# 4-20.net
KiCad netlist of a schematic drawn in Altium Designer
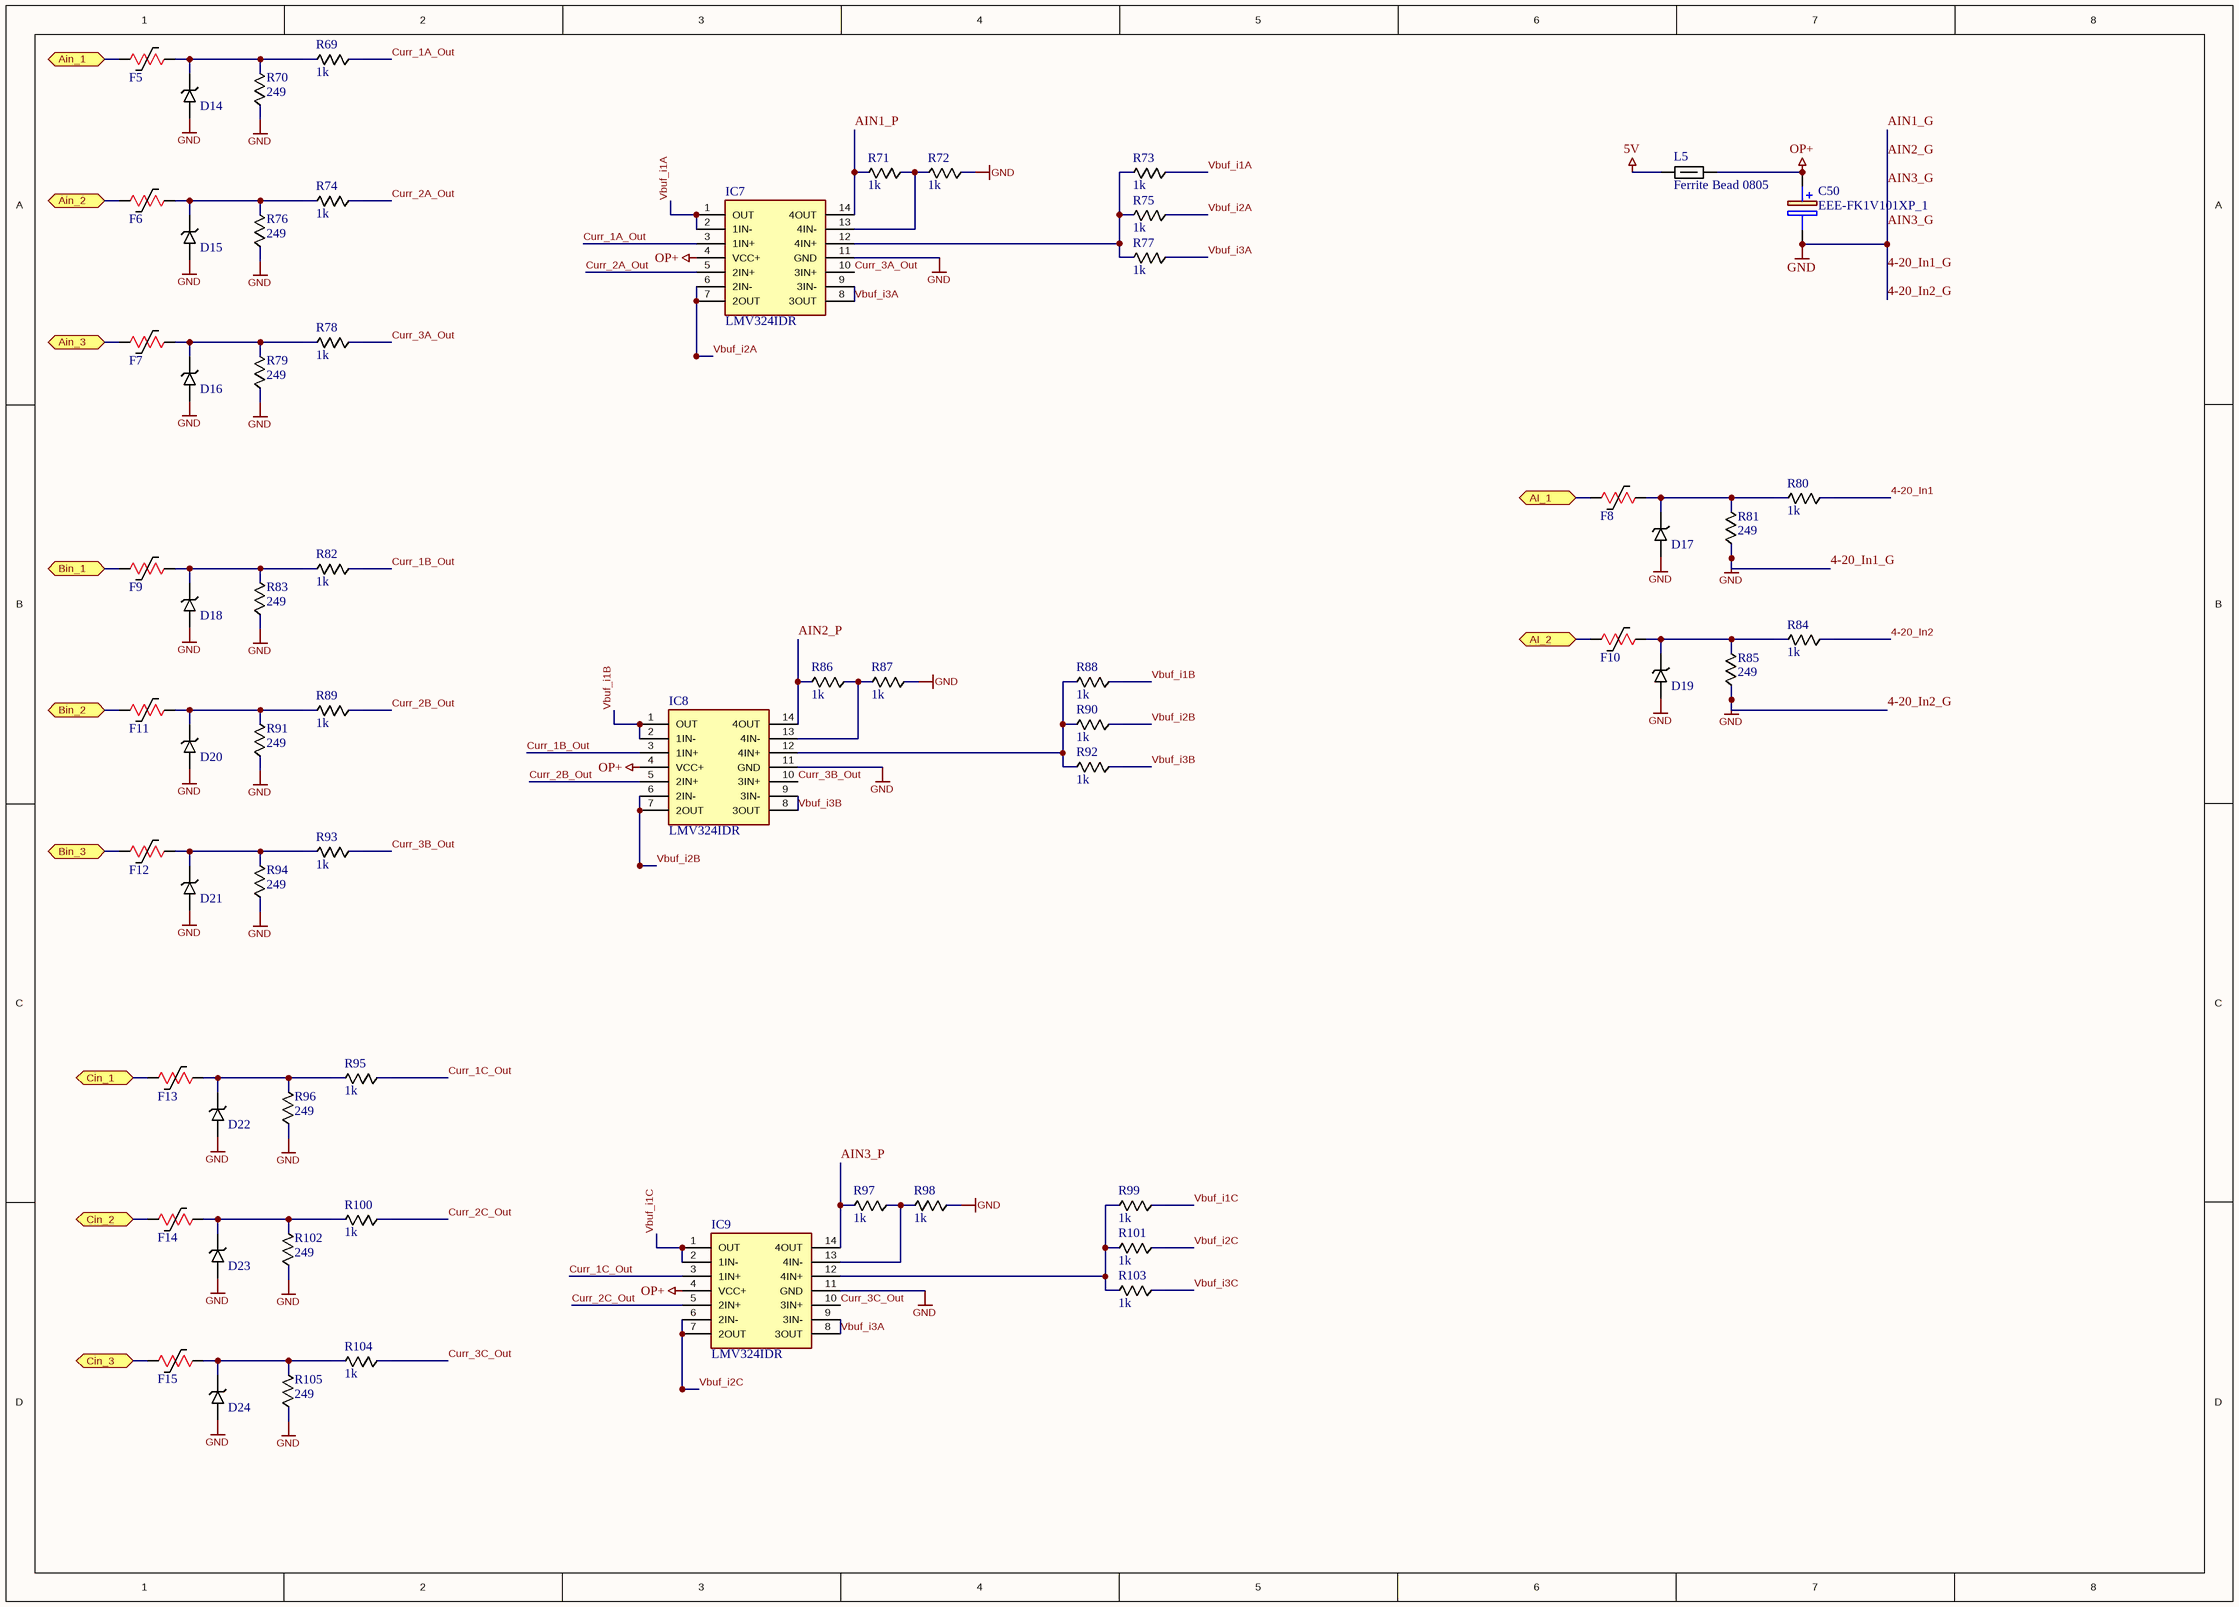
[diagram p0: 4-20.SchDoc]

(export (version "E")
  (design (tool "Eeschema 10.0.6"))
  (components
    (comp (ref "C50")
      (value "EEE-FK1V101XP_1")
      (footprint "IGAS Elements:EEE1AA220WR")
      (description "EEEFK1C100R")
      (fields
        (field (name "MANUFACTURER_PART_NUMBER") "EEE-FK1V101XP")
        (field (name "MOUSER PART NUMBER") "667-EEE-FK1V101XP")
      )
      (libsource (lib "IGAS Elements") (part "EEE-FK1V101XP_1"))
    )
    (comp (ref "D14")
      (value "TVS Diode")
      (footprint "DO-214AC / SMA - POL")
      (description "PESD5V0U1UB")
      (libsource (lib "IGAS Elements") (part "TVS_1_Uni_1"))
    )
    (comp (ref "D15")
      (value "TVS Diode")
      (footprint "DO-214AC / SMA - POL")
      (description "PESD5V0U1UB")
      (libsource (lib "IGAS Elements") (part "TVS_1_Uni_1"))
    )
    (comp (ref "D16")
      (value "TVS Diode")
      (footprint "DO-214AC / SMA - POL")
      (description "PESD5V0U1UB")
      (libsource (lib "IGAS Elements") (part "TVS_1_Uni_1"))
    )
    (comp (ref "D17")
      (value "TVS Diode")
      (footprint "DO-214AC / SMA - POL")
      (description "PESD5V0U1UB")
      (libsource (lib "IGAS Elements") (part "TVS_1_Uni_1"))
    )
    (comp (ref "D18")
      (value "TVS Diode")
      (footprint "DO-214AC / SMA - POL")
      (description "PESD5V0U1UB")
      (libsource (lib "IGAS Elements") (part "TVS_1_Uni_1"))
    )
    (comp (ref "D19")
      (value "TVS Diode")
      (footprint "DO-214AC / SMA - POL")
      (description "PESD5V0U1UB")
      (libsource (lib "IGAS Elements") (part "TVS_1_Uni_1"))
    )
    (comp (ref "D20")
      (value "TVS Diode")
      (footprint "DO-214AC / SMA - POL")
      (description "PESD5V0U1UB")
      (libsource (lib "IGAS Elements") (part "TVS_1_Uni_1"))
    )
    (comp (ref "D21")
      (value "TVS Diode")
      (footprint "DO-214AC / SMA - POL")
      (description "PESD5V0U1UB")
      (libsource (lib "IGAS Elements") (part "TVS_1_Uni_1"))
    )
    (comp (ref "D22")
      (value "TVS Diode")
      (footprint "DO-214AC / SMA - POL")
      (description "PESD5V0U1UB")
      (libsource (lib "IGAS Elements") (part "TVS_1_Uni_1"))
    )
    (comp (ref "D23")
      (value "TVS Diode")
      (footprint "DO-214AC / SMA - POL")
      (description "PESD5V0U1UB")
      (libsource (lib "IGAS Elements") (part "TVS_1_Uni_1"))
    )
    (comp (ref "D24")
      (value "TVS Diode")
      (footprint "DO-214AC / SMA - POL")
      (description "PESD5V0U1UB")
      (libsource (lib "IGAS Elements") (part "TVS_1_Uni_1"))
    )
    (comp (ref "F5")
      (value "MF-USMF005-2")
      (footprint "MF-MSMF030-2")
      (description "Resettable Fuse Polyswitch")
      (libsource (lib "IGAS Elements") (part "Fuse Resettable"))
    )
    (comp (ref "F6")
      (value "MF-USMF005-2")
      (footprint "MF-MSMF030-2")
      (description "Resettable Fuse Polyswitch")
      (libsource (lib "IGAS Elements") (part "Fuse Resettable"))
    )
    (comp (ref "F7")
      (value "MF-USMF005-2")
      (footprint "MF-MSMF030-2")
      (description "Resettable Fuse Polyswitch")
      (libsource (lib "IGAS Elements") (part "Fuse Resettable"))
    )
    (comp (ref "F8")
      (value "MF-USMF005-2")
      (footprint "MF-MSMF030-2")
      (description "Resettable Fuse Polyswitch")
      (libsource (lib "IGAS Elements") (part "Fuse Resettable"))
    )
    (comp (ref "F9")
      (value "MF-USMF005-2")
      (footprint "MF-MSMF030-2")
      (description "Resettable Fuse Polyswitch")
      (libsource (lib "IGAS Elements") (part "Fuse Resettable"))
    )
    (comp (ref "F10")
      (value "MF-USMF005-2")
      (footprint "MF-MSMF030-2")
      (description "Resettable Fuse Polyswitch")
      (libsource (lib "IGAS Elements") (part "Fuse Resettable"))
    )
    (comp (ref "F11")
      (value "MF-USMF005-2")
      (footprint "MF-MSMF030-2")
      (description "Resettable Fuse Polyswitch")
      (libsource (lib "IGAS Elements") (part "Fuse Resettable"))
    )
    (comp (ref "F12")
      (value "MF-USMF005-2")
      (footprint "MF-MSMF030-2")
      (description "Resettable Fuse Polyswitch")
      (libsource (lib "IGAS Elements") (part "Fuse Resettable"))
    )
    (comp (ref "F13")
      (value "MF-USMF005-2")
      (footprint "MF-MSMF030-2")
      (description "Resettable Fuse Polyswitch")
      (libsource (lib "IGAS Elements") (part "Fuse Resettable"))
    )
    (comp (ref "F14")
      (value "MF-USMF005-2")
      (footprint "MF-MSMF030-2")
      (description "Resettable Fuse Polyswitch")
      (libsource (lib "IGAS Elements") (part "Fuse Resettable"))
    )
    (comp (ref "F15")
      (value "MF-USMF005-2")
      (footprint "MF-MSMF030-2")
      (description "Resettable Fuse Polyswitch")
      (libsource (lib "IGAS Elements") (part "Fuse Resettable"))
    )
    (comp (ref "IC7")
      (value "LMV324IDR")
      (footprint "IGAS Elements:SOIC14N")
      (description "Integrated Circuit")
      (fields (field (name "MOUSER PART NUMBER") "595-LMV324IDR"))
      (libsource (lib "IGAS Elements") (part "LMV324IDR"))
    )
    (comp (ref "IC8")
      (value "LMV324IDR")
      (footprint "IGAS Elements:SOIC14N")
      (description "Integrated Circuit")
      (fields (field (name "MOUSER PART NUMBER") "595-LMV324IDR"))
      (libsource (lib "IGAS Elements") (part "LMV324IDR"))
    )
    (comp (ref "IC9")
      (value "LMV324IDR")
      (footprint "IGAS Elements:SOIC14N")
      (description "Integrated Circuit")
      (fields (field (name "MOUSER PART NUMBER") "595-LMV324IDR"))
      (libsource (lib "IGAS Elements") (part "LMV324IDR"))
    )
    (comp (ref "L5")
      (value "Ferrite Bead 0805")
      (footprint "BLM21AG102BH1J")
      (libsource (lib "IGAS Elements") (part "Ferrite Bead"))
    )
    (comp (ref "R69") (value "1k") (footprint "0603 CAP") (libsource (lib "IGAS Elements") (part "0603 RES")))
    (comp (ref "R70")
      (value "249")
      (footprint "1206 Res")
      (description "RC1206FR-07249RL")
      (libsource (lib "IGAS Elements") (part "RES 1206"))
    )
    (comp (ref "R71") (value "1k") (footprint "0603 CAP") (libsource (lib "IGAS Elements") (part "0603 RES")))
    (comp (ref "R72") (value "1k") (footprint "0603 CAP") (libsource (lib "IGAS Elements") (part "0603 RES")))
    (comp (ref "R73") (value "1k") (footprint "0603 CAP") (libsource (lib "IGAS Elements") (part "0603 RES")))
    (comp (ref "R74") (value "1k") (footprint "0603 CAP") (libsource (lib "IGAS Elements") (part "0603 RES")))
    (comp (ref "R75") (value "1k") (footprint "0603 CAP") (libsource (lib "IGAS Elements") (part "0603 RES")))
    (comp (ref "R76")
      (value "249")
      (footprint "1206 Res Kelvin")
      (description "RT1206BRD07249RL")
      (libsource (lib "IGAS Elements") (part "RES 1206"))
    )
    (comp (ref "R77") (value "1k") (footprint "0603 CAP") (libsource (lib "IGAS Elements") (part "0603 RES")))
    (comp (ref "R78") (value "1k") (footprint "0603 CAP") (libsource (lib "IGAS Elements") (part "0603 RES")))
    (comp (ref "R79")
      (value "249")
      (footprint "1206 Res Kelvin")
      (description "RT1206BRD07249RL")
      (libsource (lib "IGAS Elements") (part "RES 1206"))
    )
    (comp (ref "R80") (value "1k") (footprint "0603 CAP") (libsource (lib "IGAS Elements") (part "0603 RES")))
    (comp (ref "R81")
      (value "249")
      (footprint "1206 Res Kelvin")
      (description "RT1206BRD07249RL")
      (libsource (lib "IGAS Elements") (part "RES 1206"))
    )
    (comp (ref "R82") (value "1k") (footprint "0603 CAP") (libsource (lib "IGAS Elements") (part "0603 RES")))
    (comp (ref "R83")
      (value "249")
      (footprint "1206 Res Kelvin")
      (description "RT1206BRD07249RL")
      (libsource (lib "IGAS Elements") (part "RES 1206"))
    )
    (comp (ref "R84") (value "1k") (footprint "0603 CAP") (libsource (lib "IGAS Elements") (part "0603 RES")))
    (comp (ref "R85")
      (value "249")
      (footprint "1206 Res Kelvin")
      (description "RT1206BRD07249RL")
      (libsource (lib "IGAS Elements") (part "RES 1206"))
    )
    (comp (ref "R86") (value "1k") (footprint "0603 CAP") (libsource (lib "IGAS Elements") (part "0603 RES")))
    (comp (ref "R87") (value "1k") (footprint "0603 CAP") (libsource (lib "IGAS Elements") (part "0603 RES")))
    (comp (ref "R88") (value "1k") (footprint "0603 CAP") (libsource (lib "IGAS Elements") (part "0603 RES")))
    (comp (ref "R89") (value "1k") (footprint "0603 CAP") (libsource (lib "IGAS Elements") (part "0603 RES")))
    (comp (ref "R90") (value "1k") (footprint "0603 CAP") (libsource (lib "IGAS Elements") (part "0603 RES")))
    (comp (ref "R91")
      (value "249")
      (footprint "1206 Res Kelvin")
      (description "RT1206BRD07249RL")
      (libsource (lib "IGAS Elements") (part "RES 1206"))
    )
    (comp (ref "R92") (value "1k") (footprint "0603 CAP") (libsource (lib "IGAS Elements") (part "0603 RES")))
    (comp (ref "R93") (value "1k") (footprint "0603 CAP") (libsource (lib "IGAS Elements") (part "0603 RES")))
    (comp (ref "R94")
      (value "249")
      (footprint "1206 Res Kelvin")
      (description "RT1206BRD07249RL")
      (libsource (lib "IGAS Elements") (part "RES 1206"))
    )
    (comp (ref "R95") (value "1k") (footprint "0603 CAP") (libsource (lib "IGAS Elements") (part "0603 RES")))
    (comp (ref "R96")
      (value "249")
      (footprint "1206 Res Kelvin")
      (description "RT1206BRD07249RL")
      (libsource (lib "IGAS Elements") (part "RES 1206"))
    )
    (comp (ref "R97") (value "1k") (footprint "0603 CAP") (libsource (lib "IGAS Elements") (part "0603 RES")))
    (comp (ref "R98") (value "1k") (footprint "0603 CAP") (libsource (lib "IGAS Elements") (part "0603 RES")))
    (comp (ref "R99") (value "1k") (footprint "0603 CAP") (libsource (lib "IGAS Elements") (part "0603 RES")))
    (comp (ref "R100")
      (value "1k")
      (footprint "0603 CAP")
      (libsource (lib "IGAS Elements") (part "0603 RES"))
    )
    (comp (ref "R101")
      (value "1k")
      (footprint "0603 CAP")
      (libsource (lib "IGAS Elements") (part "0603 RES"))
    )
    (comp (ref "R102")
      (value "249")
      (footprint "1206 Res Kelvin")
      (description "RT1206BRD07249RL")
      (libsource (lib "IGAS Elements") (part "RES 1206"))
    )
    (comp (ref "R103")
      (value "1k")
      (footprint "0603 CAP")
      (libsource (lib "IGAS Elements") (part "0603 RES"))
    )
    (comp (ref "R104")
      (value "1k")
      (footprint "0603 CAP")
      (libsource (lib "IGAS Elements") (part "0603 RES"))
    )
    (comp (ref "R105")
      (value "249")
      (footprint "1206 Res Kelvin")
      (description "RT1206BRD07249RL")
      (libsource (lib "IGAS Elements") (part "RES 1206"))
    )
  )
  (nets
    (net (code "1") (name "/4-20_In1") (class "Default") (node (ref "R80") (pin "1") (pintype "passive")))
    (net (code "2") (name "/4-20_In2") (class "Default") (node (ref "R84") (pin "1") (pintype "passive")))
    (net (code "3") (name "/AIN1_P") (class "Default")
      (node (ref "IC7") (pin "14") (pinfunction "4OUT_14") (pintype "passive"))
      (node (ref "R71") (pin "2") (pintype "passive"))
    )
    (net (code "4") (name "/AIN2_P") (class "Default")
      (node (ref "IC8") (pin "14") (pinfunction "4OUT_14") (pintype "passive"))
      (node (ref "R86") (pin "2") (pintype "passive"))
    )
    (net (code "5") (name "/AIN3_P") (class "Default")
      (node (ref "IC9") (pin "14") (pinfunction "4OUT_14") (pintype "passive"))
      (node (ref "R97") (pin "2") (pintype "passive"))
    )
    (net (code "6") (name "/AI_1") (class "Default")
      (node (ref "F8") (pin "2") (pinfunction "2_2") (pintype "passive"))
    )
    (net (code "7") (name "/AI_2") (class "Default")
      (node (ref "F10") (pin "2") (pinfunction "2_2") (pintype "passive"))
    )
    (net (code "8") (name "/Ain_1") (class "Default")
      (node (ref "F5") (pin "2") (pinfunction "2_2") (pintype "passive"))
    )
    (net (code "9") (name "/Ain_2") (class "Default")
      (node (ref "F6") (pin "2") (pinfunction "2_2") (pintype "passive"))
    )
    (net (code "10") (name "/Ain_3") (class "Default")
      (node (ref "F7") (pin "2") (pinfunction "2_2") (pintype "passive"))
    )
    (net (code "11") (name "/Bin_1") (class "Default")
      (node (ref "F9") (pin "2") (pinfunction "2_2") (pintype "passive"))
    )
    (net (code "12") (name "/Bin_2") (class "Default")
      (node (ref "F11") (pin "2") (pinfunction "2_2") (pintype "passive"))
    )
    (net (code "13") (name "/Bin_3") (class "Default")
      (node (ref "F12") (pin "2") (pinfunction "2_2") (pintype "passive"))
    )
    (net (code "14") (name "/Cin_1") (class "Default")
      (node (ref "F13") (pin "2") (pinfunction "2_2") (pintype "passive"))
    )
    (net (code "15") (name "/Cin_2") (class "Default")
      (node (ref "F14") (pin "2") (pinfunction "2_2") (pintype "passive"))
    )
    (net (code "16") (name "/Cin_3") (class "Default")
      (node (ref "F15") (pin "2") (pinfunction "2_2") (pintype "passive"))
    )
    (net (code "17") (name "/Curr_1A_Out") (class "Default")
      (node (ref "IC7") (pin "3") (pinfunction "1IN+_3") (pintype "passive"))
      (node (ref "R69") (pin "1") (pintype "passive"))
    )
    (net (code "18") (name "/Curr_1B_Out") (class "Default")
      (node (ref "IC8") (pin "3") (pinfunction "1IN+_3") (pintype "passive"))
      (node (ref "R82") (pin "1") (pintype "passive"))
    )
    (net (code "19") (name "/Curr_1C_Out") (class "Default")
      (node (ref "IC9") (pin "3") (pinfunction "1IN+_3") (pintype "passive"))
      (node (ref "R95") (pin "1") (pintype "passive"))
    )
    (net (code "20") (name "/Curr_2A_Out") (class "Default")
      (node (ref "IC7") (pin "5") (pinfunction "2IN+_5") (pintype "passive"))
      (node (ref "R74") (pin "1") (pintype "passive"))
    )
    (net (code "21") (name "/Curr_2B_Out") (class "Default")
      (node (ref "IC8") (pin "5") (pinfunction "2IN+_5") (pintype "passive"))
      (node (ref "R89") (pin "1") (pintype "passive"))
    )
    (net (code "22") (name "/Curr_2C_Out") (class "Default")
      (node (ref "IC9") (pin "5") (pinfunction "2IN+_5") (pintype "passive"))
      (node (ref "R100") (pin "1") (pintype "passive"))
    )
    (net (code "23") (name "/Curr_3A_Out") (class "Default")
      (node (ref "IC7") (pin "10") (pinfunction "3IN+_10") (pintype "passive"))
      (node (ref "R78") (pin "1") (pintype "passive"))
    )
    (net (code "24") (name "/Curr_3B_Out") (class "Default")
      (node (ref "IC8") (pin "10") (pinfunction "3IN+_10") (pintype "passive"))
      (node (ref "R93") (pin "1") (pintype "passive"))
    )
    (net (code "25") (name "/Curr_3C_Out") (class "Default")
      (node (ref "IC9") (pin "10") (pinfunction "3IN+_10") (pintype "passive"))
      (node (ref "R104") (pin "1") (pintype "passive"))
    )
    (net (code "26") (name "/Vbuf_i1A") (class "Default")
      (node (ref "IC7") (pin "1") (pinfunction "OUT_1") (pintype "passive"))
      (node (ref "IC7") (pin "2") (pinfunction "1IN-_2") (pintype "passive"))
      (node (ref "R73") (pin "1") (pintype "passive"))
    )
    (net (code "27") (name "/Vbuf_i1B") (class "Default")
      (node (ref "IC8") (pin "1") (pinfunction "OUT_1") (pintype "passive"))
      (node (ref "IC8") (pin "2") (pinfunction "1IN-_2") (pintype "passive"))
      (node (ref "R88") (pin "1") (pintype "passive"))
    )
    (net (code "28") (name "/Vbuf_i1C") (class "Default")
      (node (ref "IC9") (pin "1") (pinfunction "OUT_1") (pintype "passive"))
      (node (ref "IC9") (pin "2") (pinfunction "1IN-_2") (pintype "passive"))
      (node (ref "R99") (pin "1") (pintype "passive"))
    )
    (net (code "29") (name "/Vbuf_i2A") (class "Default")
      (node (ref "IC7") (pin "6") (pinfunction "2IN-_6") (pintype "passive"))
      (node (ref "IC7") (pin "7") (pinfunction "2OUT_7") (pintype "passive"))
      (node (ref "R75") (pin "1") (pintype "passive"))
    )
    (net (code "30") (name "/Vbuf_i2B") (class "Default")
      (node (ref "IC8") (pin "6") (pinfunction "2IN-_6") (pintype "passive"))
      (node (ref "IC8") (pin "7") (pinfunction "2OUT_7") (pintype "passive"))
      (node (ref "R90") (pin "1") (pintype "passive"))
    )
    (net (code "31") (name "/Vbuf_i2C") (class "Default")
      (node (ref "IC9") (pin "6") (pinfunction "2IN-_6") (pintype "passive"))
      (node (ref "IC9") (pin "7") (pinfunction "2OUT_7") (pintype "passive"))
      (node (ref "R101") (pin "1") (pintype "passive"))
    )
    (net (code "32") (name "/Vbuf_i3A") (class "Default")
      (node (ref "IC7") (pin "8") (pinfunction "3OUT_8") (pintype "passive"))
      (node (ref "IC7") (pin "9") (pinfunction "3IN-_9") (pintype "passive"))
      (node (ref "IC9") (pin "8") (pinfunction "3OUT_8") (pintype "passive"))
      (node (ref "IC9") (pin "9") (pinfunction "3IN-_9") (pintype "passive"))
      (node (ref "R77") (pin "1") (pintype "passive"))
    )
    (net (code "33") (name "/Vbuf_i3B") (class "Default")
      (node (ref "IC8") (pin "8") (pinfunction "3OUT_8") (pintype "passive"))
      (node (ref "IC8") (pin "9") (pinfunction "3IN-_9") (pintype "passive"))
      (node (ref "R92") (pin "1") (pintype "passive"))
    )
    (net (code "34") (name "/Vbuf_i3C") (class "Default") (node (ref "R103") (pin "1") (pintype "passive")))
    (net (code "35") (name "5V") (class "Default")
      (node (ref "L5") (pin "1") (pinfunction "1_1") (pintype "passive"))
    )
    (net (code "36") (name "GND") (class "Default")
      (node (ref "C50") (pin "2") (pinfunction "-_2") (pintype "passive"))
      (node (ref "D14") (pin "1") (pinfunction "1_1") (pintype "passive"))
      (node (ref "D15") (pin "1") (pinfunction "1_1") (pintype "passive"))
      (node (ref "D16") (pin "1") (pinfunction "1_1") (pintype "passive"))
      (node (ref "D17") (pin "1") (pinfunction "1_1") (pintype "passive"))
      (node (ref "D18") (pin "1") (pinfunction "1_1") (pintype "passive"))
      (node (ref "D19") (pin "1") (pinfunction "1_1") (pintype "passive"))
      (node (ref "D20") (pin "1") (pinfunction "1_1") (pintype "passive"))
      (node (ref "D21") (pin "1") (pinfunction "1_1") (pintype "passive"))
      (node (ref "D22") (pin "1") (pinfunction "1_1") (pintype "passive"))
      (node (ref "D23") (pin "1") (pinfunction "1_1") (pintype "passive"))
      (node (ref "D24") (pin "1") (pinfunction "1_1") (pintype "passive"))
      (node (ref "IC7") (pin "11") (pinfunction "GND_11") (pintype "passive"))
      (node (ref "IC8") (pin "11") (pinfunction "GND_11") (pintype "passive"))
      (node (ref "IC9") (pin "11") (pinfunction "GND_11") (pintype "passive"))
      (node (ref "R102") (pin "1") (pintype "passive"))
      (node (ref "R105") (pin "1") (pintype "passive"))
      (node (ref "R70") (pin "1") (pintype "passive"))
      (node (ref "R72") (pin "1") (pintype "passive"))
      (node (ref "R76") (pin "1") (pintype "passive"))
      (node (ref "R79") (pin "1") (pintype "passive"))
      (node (ref "R81") (pin "1") (pintype "passive"))
      (node (ref "R83") (pin "1") (pintype "passive"))
      (node (ref "R85") (pin "1") (pintype "passive"))
      (node (ref "R87") (pin "1") (pintype "passive"))
      (node (ref "R91") (pin "1") (pintype "passive"))
      (node (ref "R94") (pin "1") (pintype "passive"))
      (node (ref "R96") (pin "1") (pintype "passive"))
      (node (ref "R98") (pin "1") (pintype "passive"))
    )
    (net (code "37") (name "Net-(D14-Pad2)") (class "Default")
      (node (ref "D14") (pin "2") (pinfunction "2_2") (pintype "passive"))
      (node (ref "F5") (pin "1") (pinfunction "1_1") (pintype "passive"))
      (node (ref "R69") (pin "2") (pintype "passive"))
      (node (ref "R70") (pin "2") (pintype "passive"))
    )
    (net (code "38") (name "Net-(D15-Pad2)") (class "Default")
      (node (ref "D15") (pin "2") (pinfunction "2_2") (pintype "passive"))
      (node (ref "F6") (pin "1") (pinfunction "1_1") (pintype "passive"))
      (node (ref "R74") (pin "2") (pintype "passive"))
      (node (ref "R76") (pin "2") (pintype "passive"))
    )
    (net (code "39") (name "Net-(D16-Pad2)") (class "Default")
      (node (ref "D16") (pin "2") (pinfunction "2_2") (pintype "passive"))
      (node (ref "F7") (pin "1") (pinfunction "1_1") (pintype "passive"))
      (node (ref "R78") (pin "2") (pintype "passive"))
      (node (ref "R79") (pin "2") (pintype "passive"))
    )
    (net (code "40") (name "Net-(D17-Pad2)") (class "Default")
      (node (ref "D17") (pin "2") (pinfunction "2_2") (pintype "passive"))
      (node (ref "F8") (pin "1") (pinfunction "1_1") (pintype "passive"))
      (node (ref "R80") (pin "2") (pintype "passive"))
      (node (ref "R81") (pin "2") (pintype "passive"))
    )
    (net (code "41") (name "Net-(D18-Pad2)") (class "Default")
      (node (ref "D18") (pin "2") (pinfunction "2_2") (pintype "passive"))
      (node (ref "F9") (pin "1") (pinfunction "1_1") (pintype "passive"))
      (node (ref "R82") (pin "2") (pintype "passive"))
      (node (ref "R83") (pin "2") (pintype "passive"))
    )
    (net (code "42") (name "Net-(D19-Pad2)") (class "Default")
      (node (ref "D19") (pin "2") (pinfunction "2_2") (pintype "passive"))
      (node (ref "F10") (pin "1") (pinfunction "1_1") (pintype "passive"))
      (node (ref "R84") (pin "2") (pintype "passive"))
      (node (ref "R85") (pin "2") (pintype "passive"))
    )
    (net (code "43") (name "Net-(D20-Pad2)") (class "Default")
      (node (ref "D20") (pin "2") (pinfunction "2_2") (pintype "passive"))
      (node (ref "F11") (pin "1") (pinfunction "1_1") (pintype "passive"))
      (node (ref "R89") (pin "2") (pintype "passive"))
      (node (ref "R91") (pin "2") (pintype "passive"))
    )
    (net (code "44") (name "Net-(D21-Pad2)") (class "Default")
      (node (ref "D21") (pin "2") (pinfunction "2_2") (pintype "passive"))
      (node (ref "F12") (pin "1") (pinfunction "1_1") (pintype "passive"))
      (node (ref "R93") (pin "2") (pintype "passive"))
      (node (ref "R94") (pin "2") (pintype "passive"))
    )
    (net (code "45") (name "Net-(D22-Pad2)") (class "Default")
      (node (ref "D22") (pin "2") (pinfunction "2_2") (pintype "passive"))
      (node (ref "F13") (pin "1") (pinfunction "1_1") (pintype "passive"))
      (node (ref "R95") (pin "2") (pintype "passive"))
      (node (ref "R96") (pin "2") (pintype "passive"))
    )
    (net (code "46") (name "Net-(D23-Pad2)") (class "Default")
      (node (ref "D23") (pin "2") (pinfunction "2_2") (pintype "passive"))
      (node (ref "F14") (pin "1") (pinfunction "1_1") (pintype "passive"))
      (node (ref "R100") (pin "2") (pintype "passive"))
      (node (ref "R102") (pin "2") (pintype "passive"))
    )
    (net (code "47") (name "Net-(D24-Pad2)") (class "Default")
      (node (ref "D24") (pin "2") (pinfunction "2_2") (pintype "passive"))
      (node (ref "F15") (pin "1") (pinfunction "1_1") (pintype "passive"))
      (node (ref "R104") (pin "2") (pintype "passive"))
      (node (ref "R105") (pin "2") (pintype "passive"))
    )
    (net (code "48") (name "Net-(IC7-4IN+)") (class "Default")
      (node (ref "IC7") (pin "12") (pinfunction "4IN+_12") (pintype "passive"))
      (node (ref "R73") (pin "2") (pintype "passive"))
      (node (ref "R75") (pin "2") (pintype "passive"))
      (node (ref "R77") (pin "2") (pintype "passive"))
    )
    (net (code "49") (name "Net-(IC7-4IN-)") (class "Default")
      (node (ref "IC7") (pin "13") (pinfunction "4IN-_13") (pintype "passive"))
      (node (ref "R71") (pin "1") (pintype "passive"))
      (node (ref "R72") (pin "2") (pintype "passive"))
    )
    (net (code "50") (name "Net-(IC8-4IN+)") (class "Default")
      (node (ref "IC8") (pin "12") (pinfunction "4IN+_12") (pintype "passive"))
      (node (ref "R88") (pin "2") (pintype "passive"))
      (node (ref "R90") (pin "2") (pintype "passive"))
      (node (ref "R92") (pin "2") (pintype "passive"))
    )
    (net (code "51") (name "Net-(IC8-4IN-)") (class "Default")
      (node (ref "IC8") (pin "13") (pinfunction "4IN-_13") (pintype "passive"))
      (node (ref "R86") (pin "1") (pintype "passive"))
      (node (ref "R87") (pin "2") (pintype "passive"))
    )
    (net (code "52") (name "Net-(IC9-4IN+)") (class "Default")
      (node (ref "IC9") (pin "12") (pinfunction "4IN+_12") (pintype "passive"))
      (node (ref "R101") (pin "2") (pintype "passive"))
      (node (ref "R103") (pin "2") (pintype "passive"))
      (node (ref "R99") (pin "2") (pintype "passive"))
    )
    (net (code "53") (name "Net-(IC9-4IN-)") (class "Default")
      (node (ref "IC9") (pin "13") (pinfunction "4IN-_13") (pintype "passive"))
      (node (ref "R97") (pin "1") (pintype "passive"))
      (node (ref "R98") (pin "2") (pintype "passive"))
    )
    (net (code "54") (name "OP+") (class "Default")
      (node (ref "C50") (pin "1") (pinfunction "+_1") (pintype "passive"))
      (node (ref "IC7") (pin "4") (pinfunction "VCC+_4") (pintype "passive"))
      (node (ref "IC8") (pin "4") (pinfunction "VCC+_4") (pintype "passive"))
      (node (ref "IC9") (pin "4") (pinfunction "VCC+_4") (pintype "passive"))
      (node (ref "L5") (pin "2") (pinfunction "2_2") (pintype "passive"))
    )
  )
)
